# schChaves.net
KiCad netlist of a schematic drawn in Altium Designer
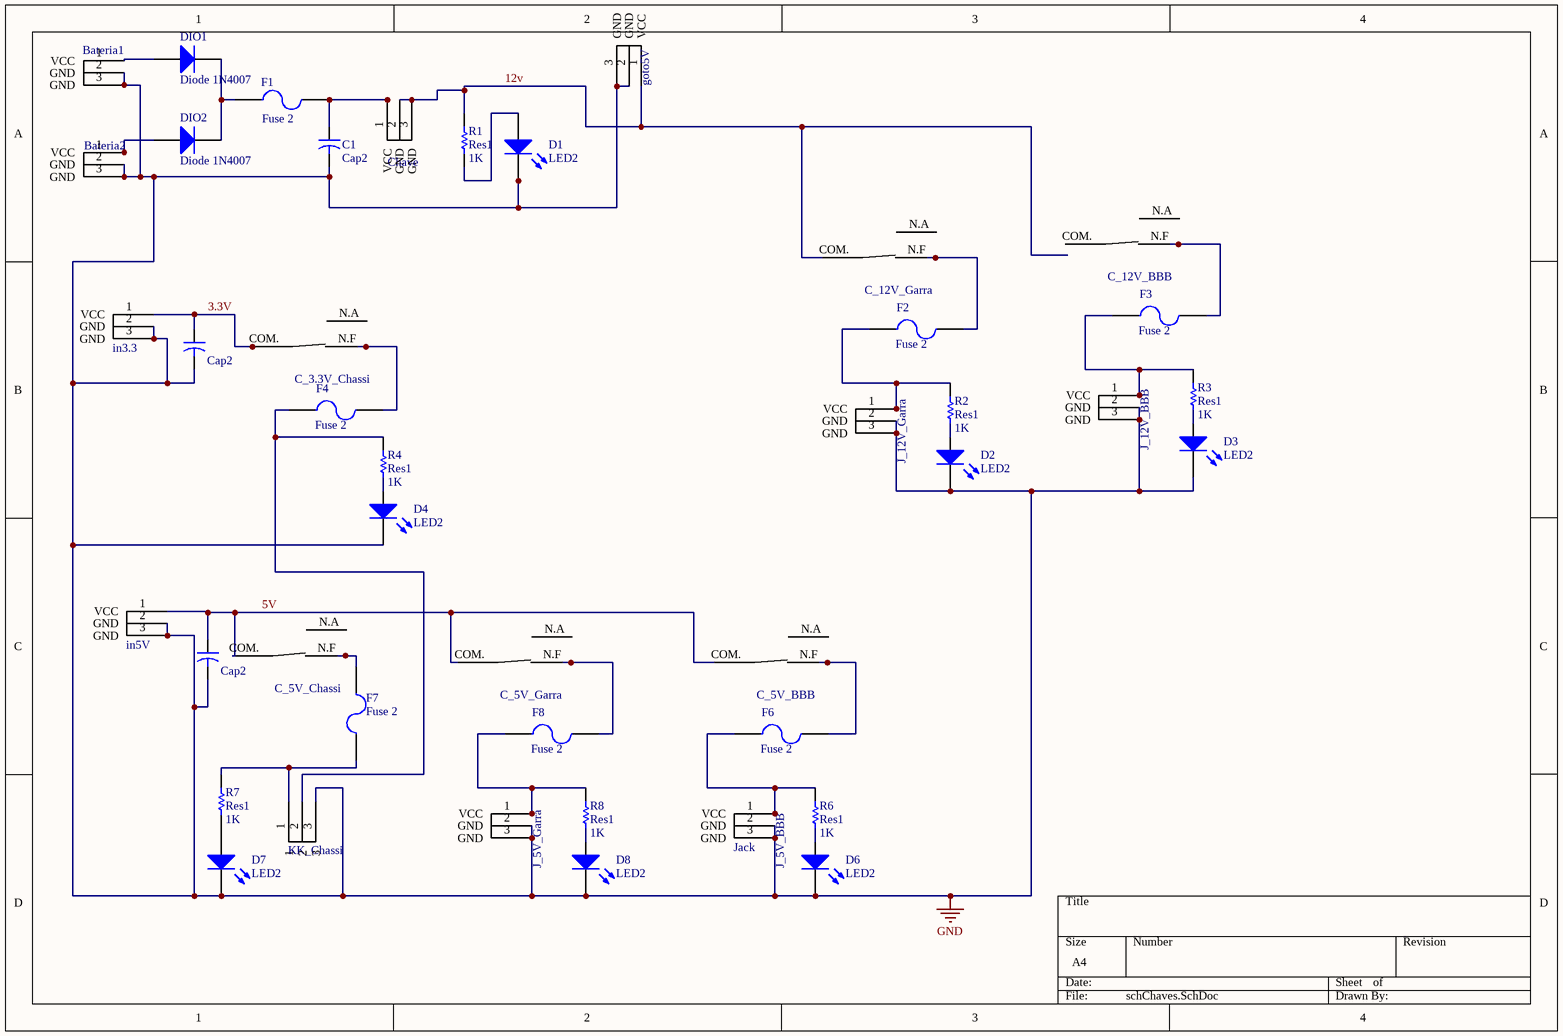
[diagram p0: schChaves.SchDoc]

(export (version "E")
  (design (tool "Eeschema 10.0.6"))
  (components
    (comp (ref "Bateria1")
      (value "Jack")
      (footprint "JACK J4")
      (libsource (lib "Componentes_Open") (part "Jack"))
    )
    (comp (ref "Bateria2")
      (value "Jack")
      (footprint "JACK J4")
      (libsource (lib "Componentes_Open") (part "Jack"))
    )
    (comp (ref "C1")
      (value "Cap2")
      (footprint "RAD-0.2")
      (description "Capacitor")
      (fields (field (name "PUBLISHER") "Altium Limited"))
      (libsource (lib "Miscellaneous Devices") (part "Cap2"))
    )
    (comp (ref "C3")
      (value "Cap2")
      (footprint "RAD-0.2")
      (description "Capacitor")
      (fields (field (name "PUBLISHER") "Altium Limited"))
      (libsource (lib "Miscellaneous Devices") (part "Cap2"))
    )
    (comp (ref "C5")
      (value "Cap2")
      (footprint "RAD-0.2")
      (description "Capacitor")
      (fields (field (name "PUBLISHER") "Altium Limited"))
      (libsource (lib "Miscellaneous Devices") (part "Cap2"))
    )
    (comp (ref "Chave")
      (value "Jack")
      (footprint "JACK J4")
      (libsource (lib "Componentes_Open") (part "Jack"))
    )
    (comp (ref "C_3.3V_Chassi")
      (value "Chave")
      (footprint "Chave")
      (libsource (lib "Componentes_Open") (part "Chave"))
    )
    (comp (ref "C_5V_BBB")
      (value "Chave")
      (footprint "Chave")
      (libsource (lib "Componentes_Open") (part "Chave"))
    )
    (comp (ref "C_5V_Chassi")
      (value "Chave")
      (footprint "Chave")
      (libsource (lib "Componentes_Open") (part "Chave"))
    )
    (comp (ref "C_5V_Garra")
      (value "Chave")
      (footprint "Chave")
      (libsource (lib "Componentes_Open") (part "Chave"))
    )
    (comp (ref "C_12V_BBB")
      (value "Chave")
      (footprint "Chave")
      (libsource (lib "Componentes_Open") (part "Chave"))
    )
    (comp (ref "C_12V_Garra")
      (value "Chave")
      (footprint "Chave")
      (libsource (lib "Componentes_Open") (part "Chave"))
    )
    (comp (ref "D1")
      (value "LED2")
      (footprint "3.2X1.6X1.1")
      (description "Typical RED, GREEN, YELLOW, AMBER GaAs LED")
      (fields (field (name "PUBLISHER") "Altium Limited"))
      (libsource (lib "Miscellaneous Devices") (part "LED2"))
    )
    (comp (ref "D2")
      (value "LED2")
      (footprint "3.2X1.6X1.1")
      (description "Typical RED, GREEN, YELLOW, AMBER GaAs LED")
      (fields (field (name "PUBLISHER") "Altium Limited"))
      (libsource (lib "Miscellaneous Devices") (part "LED2"))
    )
    (comp (ref "D3")
      (value "LED2")
      (footprint "3.2X1.6X1.1")
      (description "Typical RED, GREEN, YELLOW, AMBER GaAs LED")
      (fields (field (name "PUBLISHER") "Altium Limited"))
      (libsource (lib "Miscellaneous Devices") (part "LED2"))
    )
    (comp (ref "D4")
      (value "LED2")
      (footprint "3.2X1.6X1.1")
      (description "Typical RED, GREEN, YELLOW, AMBER GaAs LED")
      (fields (field (name "PUBLISHER") "Altium Limited"))
      (libsource (lib "Miscellaneous Devices") (part "LED2"))
    )
    (comp (ref "D6")
      (value "LED2")
      (footprint "3.2X1.6X1.1")
      (description "Typical RED, GREEN, YELLOW, AMBER GaAs LED")
      (fields (field (name "PUBLISHER") "Altium Limited"))
      (libsource (lib "Miscellaneous Devices") (part "LED2"))
    )
    (comp (ref "D7")
      (value "LED2")
      (footprint "3.2X1.6X1.1")
      (description "Typical RED, GREEN, YELLOW, AMBER GaAs LED")
      (fields (field (name "PUBLISHER") "Altium Limited"))
      (libsource (lib "Miscellaneous Devices") (part "LED2"))
    )
    (comp (ref "D8")
      (value "LED2")
      (footprint "3.2X1.6X1.1")
      (description "Typical RED, GREEN, YELLOW, AMBER GaAs LED")
      (fields (field (name "PUBLISHER") "Altium Limited"))
      (libsource (lib "Miscellaneous Devices") (part "LED2"))
    )
    (comp (ref "DIO1")
      (value "Diode 1N4007")
      (footprint "DO-41")
      (description "1 Amp General Purpose Rectifier")
      (fields (field (name "PUBLISHER") "Altium Limited"))
      (libsource (lib "Miscellaneous Devices") (part "Diode 1N4007"))
    )
    (comp (ref "DIO2")
      (value "Diode 1N4007")
      (footprint "DO-41")
      (description "1 Amp General Purpose Rectifier")
      (fields (field (name "PUBLISHER") "Altium Limited"))
      (libsource (lib "Miscellaneous Devices") (part "Diode 1N4007"))
    )
    (comp (ref "F1")
      (value "Fuse 2")
      (footprint "Fusivel")
      (description "Fuse")
      (fields (field (name "PUBLISHER") "Altium Limited"))
      (libsource (lib "Miscellaneous Devices") (part "Fuse 2"))
    )
    (comp (ref "F2")
      (value "Fuse 2")
      (footprint "Fusivel")
      (description "Fuse")
      (fields (field (name "PUBLISHER") "Altium Limited"))
      (libsource (lib "Miscellaneous Devices") (part "Fuse 2"))
    )
    (comp (ref "F3")
      (value "Fuse 2")
      (footprint "Fusivel")
      (description "Fuse")
      (fields (field (name "PUBLISHER") "Altium Limited"))
      (libsource (lib "Miscellaneous Devices") (part "Fuse 2"))
    )
    (comp (ref "F4")
      (value "Fuse 2")
      (footprint "Fusivel")
      (description "Fuse")
      (fields (field (name "PUBLISHER") "Altium Limited"))
      (libsource (lib "Miscellaneous Devices") (part "Fuse 2"))
    )
    (comp (ref "F6")
      (value "Fuse 2")
      (footprint "Fusivel")
      (description "Fuse")
      (fields (field (name "PUBLISHER") "Altium Limited"))
      (libsource (lib "Miscellaneous Devices") (part "Fuse 2"))
    )
    (comp (ref "F7")
      (value "Fuse 2")
      (footprint "Fusivel")
      (description "Fuse")
      (fields (field (name "PUBLISHER") "Altium Limited"))
      (libsource (lib "Miscellaneous Devices") (part "Fuse 2"))
    )
    (comp (ref "F8")
      (value "Fuse 2")
      (footprint "Fusivel")
      (description "Fuse")
      (fields (field (name "PUBLISHER") "Altium Limited"))
      (libsource (lib "Miscellaneous Devices") (part "Fuse 2"))
    )
    (comp (ref "goto5V")
      (value "Jack")
      (footprint "JACK J4")
      (libsource (lib "Componentes_Open") (part "Jack"))
    )
    (comp (ref "in3.3")
      (value "Jack")
      (footprint "JACK J4")
      (libsource (lib "Componentes_Open") (part "Jack"))
    )
    (comp (ref "in5V")
      (value "Jack")
      (footprint "JACK J4")
      (libsource (lib "Componentes_Open") (part "Jack"))
    )
    (comp (ref "J_5V_BBB")
      (value "Jack")
      (footprint "JACK J4")
      (libsource (lib "Componentes_Open") (part "Jack"))
    )
    (comp (ref "J_5V_Garra")
      (value "Jack")
      (footprint "JACK J4")
      (libsource (lib "Componentes_Open") (part "Jack"))
    )
    (comp (ref "J_12V_BBB")
      (value "Jack")
      (footprint "JACK J4")
      (libsource (lib "Componentes_Open") (part "Jack"))
    )
    (comp (ref "J_12V_Garra")
      (value "Jack")
      (footprint "JACK J4")
      (libsource (lib "Componentes_Open") (part "Jack"))
    )
    (comp (ref "KK_Chassi")
      (value "KK3")
      (footprint "3-vias")
      (libsource (lib "Componentes_Open") (part "KK3Vias"))
    )
    (comp (ref "R1")
      (value "Res1")
      (footprint "AXIAL-0.3")
      (description "Resistor")
      (fields (field (name "ALTIUM_VALUE") "1K") (field (name "PUBLISHER") "Altium Limited"))
      (libsource (lib "Miscellaneous Devices") (part "Res1"))
    )
    (comp (ref "R2")
      (value "Res1")
      (footprint "AXIAL-0.3")
      (description "Resistor")
      (fields (field (name "ALTIUM_VALUE") "1K") (field (name "PUBLISHER") "Altium Limited"))
      (libsource (lib "Miscellaneous Devices") (part "Res1"))
    )
    (comp (ref "R3")
      (value "Res1")
      (footprint "AXIAL-0.3")
      (description "Resistor")
      (fields (field (name "ALTIUM_VALUE") "1K") (field (name "PUBLISHER") "Altium Limited"))
      (libsource (lib "Miscellaneous Devices") (part "Res1"))
    )
    (comp (ref "R4")
      (value "Res1")
      (footprint "AXIAL-0.3")
      (description "Resistor")
      (fields (field (name "ALTIUM_VALUE") "1K") (field (name "PUBLISHER") "Altium Limited"))
      (libsource (lib "Miscellaneous Devices") (part "Res1"))
    )
    (comp (ref "R6")
      (value "Res1")
      (footprint "AXIAL-0.3")
      (description "Resistor")
      (fields (field (name "ALTIUM_VALUE") "1K") (field (name "PUBLISHER") "Altium Limited"))
      (libsource (lib "Miscellaneous Devices") (part "Res1"))
    )
    (comp (ref "R7")
      (value "Res1")
      (footprint "AXIAL-0.3")
      (description "Resistor")
      (fields (field (name "ALTIUM_VALUE") "1K") (field (name "PUBLISHER") "Altium Limited"))
      (libsource (lib "Miscellaneous Devices") (part "Res1"))
    )
    (comp (ref "R8")
      (value "Res1")
      (footprint "AXIAL-0.3")
      (description "Resistor")
      (fields (field (name "ALTIUM_VALUE") "1K") (field (name "PUBLISHER") "Altium Limited"))
      (libsource (lib "Miscellaneous Devices") (part "Res1"))
    )
  )
  (nets
    (net (code "1") (name "/3.3V") (class "Default")
      (node (ref "C3") (pin "1") (pinfunction "1_1") (pintype "passive"))
      (node (ref "C_3.3V_Chassi") (pin "COM.") (pinfunction "COM_COM.") (pintype "passive"))
      (node (ref "in3.3") (pin "1") (pinfunction "VCC_1") (pintype "passive"))
    )
    (net (code "2") (name "/5V") (class "Default")
      (node (ref "C5") (pin "1") (pinfunction "1_1") (pintype "passive"))
      (node (ref "C_5V_BBB") (pin "COM.") (pinfunction "COM_COM.") (pintype "passive"))
      (node (ref "C_5V_Chassi") (pin "COM.") (pinfunction "COM_COM.") (pintype "passive"))
      (node (ref "C_5V_Garra") (pin "COM.") (pinfunction "COM_COM.") (pintype "passive"))
      (node (ref "in5V") (pin "1") (pinfunction "VCC_1") (pintype "passive"))
    )
    (net (code "3") (name "/12v") (class "Default")
      (node (ref "C_12V_Garra") (pin "COM.") (pinfunction "COM_COM.") (pintype "passive"))
      (node (ref "Chave") (pin "2") (pinfunction "GND_2") (pintype "passive"))
      (node (ref "Chave") (pin "3") (pinfunction "GND_3") (pintype "passive"))
      (node (ref "R1") (pin "2") (pinfunction "2_2") (pintype "passive"))
      (node (ref "goto5V") (pin "1") (pinfunction "VCC_1") (pintype "passive"))
    )
    (net (code "4") (name "GND") (class "Default")
      (node (ref "Bateria1") (pin "2") (pinfunction "GND_2") (pintype "passive"))
      (node (ref "Bateria1") (pin "3") (pinfunction "GND_3") (pintype "passive"))
      (node (ref "Bateria2") (pin "2") (pinfunction "GND_2") (pintype "passive"))
      (node (ref "Bateria2") (pin "3") (pinfunction "GND_3") (pintype "passive"))
      (node (ref "C1") (pin "2") (pinfunction "2_2") (pintype "passive"))
      (node (ref "C3") (pin "2") (pinfunction "2_2") (pintype "passive"))
      (node (ref "C5") (pin "2") (pinfunction "2_2") (pintype "passive"))
      (node (ref "D1") (pin "2") (pinfunction "K_2") (pintype "passive"))
      (node (ref "D2") (pin "2") (pinfunction "K_2") (pintype "passive"))
      (node (ref "D3") (pin "2") (pinfunction "K_2") (pintype "passive"))
      (node (ref "D4") (pin "2") (pinfunction "K_2") (pintype "passive"))
      (node (ref "D6") (pin "2") (pinfunction "K_2") (pintype "passive"))
      (node (ref "D7") (pin "2") (pinfunction "K_2") (pintype "passive"))
      (node (ref "D8") (pin "2") (pinfunction "K_2") (pintype "passive"))
      (node (ref "J_12V_BBB") (pin "2") (pinfunction "GND_2") (pintype "passive"))
      (node (ref "J_12V_BBB") (pin "3") (pinfunction "GND_3") (pintype "passive"))
      (node (ref "J_12V_Garra") (pin "2") (pinfunction "GND_2") (pintype "passive"))
      (node (ref "J_12V_Garra") (pin "3") (pinfunction "GND_3") (pintype "passive"))
      (node (ref "J_5V_BBB") (pin "2") (pinfunction "GND_2") (pintype "passive"))
      (node (ref "J_5V_BBB") (pin "3") (pinfunction "GND_3") (pintype "passive"))
      (node (ref "J_5V_Garra") (pin "2") (pinfunction "GND_2") (pintype "passive"))
      (node (ref "J_5V_Garra") (pin "3") (pinfunction "GND_3") (pintype "passive"))
      (node (ref "KK_Chassi") (pin "3") (pinfunction "3_3") (pintype "passive"))
      (node (ref "goto5V") (pin "2") (pinfunction "GND_2") (pintype "passive"))
      (node (ref "goto5V") (pin "3") (pinfunction "GND_3") (pintype "passive"))
      (node (ref "in3.3") (pin "2") (pinfunction "GND_2") (pintype "passive"))
      (node (ref "in3.3") (pin "3") (pinfunction "GND_3") (pintype "passive"))
      (node (ref "in5V") (pin "2") (pinfunction "GND_2") (pintype "passive"))
      (node (ref "in5V") (pin "3") (pinfunction "GND_3") (pintype "passive"))
    )
    (net (code "5") (name "Net-(Bateria1-VCC)") (class "Default")
      (node (ref "Bateria1") (pin "1") (pinfunction "VCC_1") (pintype "passive"))
      (node (ref "DIO1") (pin "1") (pinfunction "A_1") (pintype "passive"))
    )
    (net (code "6") (name "Net-(Bateria2-VCC)") (class "Default")
      (node (ref "Bateria2") (pin "1") (pinfunction "VCC_1") (pintype "passive"))
      (node (ref "DIO2") (pin "1") (pinfunction "A_1") (pintype "passive"))
    )
    (net (code "7") (name "Net-(C_3.3V_Chassi-PadN.F)") (class "Default")
      (node (ref "C_3.3V_Chassi") (pin "N.F") (pinfunction "N.F_N.F") (pintype "passive"))
      (node (ref "F4") (pin "2") (pinfunction "2_2") (pintype "passive"))
    )
    (net (code "8") (name "Net-(C_5V_BBB-PadN.F)") (class "Default")
      (node (ref "C_5V_BBB") (pin "N.F") (pinfunction "N.F_N.F") (pintype "passive"))
      (node (ref "F6") (pin "2") (pinfunction "2_2") (pintype "passive"))
    )
    (net (code "9") (name "Net-(C_5V_Chassi-PadN.F)") (class "Default")
      (node (ref "C_5V_Chassi") (pin "N.F") (pinfunction "N.F_N.F") (pintype "passive"))
      (node (ref "F7") (pin "1") (pinfunction "1_1") (pintype "passive"))
    )
    (net (code "10") (name "Net-(C_5V_Garra-PadN.F)") (class "Default")
      (node (ref "C_5V_Garra") (pin "N.F") (pinfunction "N.F_N.F") (pintype "passive"))
      (node (ref "F8") (pin "2") (pinfunction "2_2") (pintype "passive"))
    )
    (net (code "11") (name "Net-(C_12V_BBB-PadN.F)") (class "Default")
      (node (ref "C_12V_BBB") (pin "N.F") (pinfunction "N.F_N.F") (pintype "passive"))
      (node (ref "F3") (pin "2") (pinfunction "2_2") (pintype "passive"))
    )
    (net (code "12") (name "Net-(C_12V_Garra-PadN.F)") (class "Default")
      (node (ref "C_12V_Garra") (pin "N.F") (pinfunction "N.F_N.F") (pintype "passive"))
      (node (ref "F2") (pin "2") (pinfunction "2_2") (pintype "passive"))
    )
    (net (code "13") (name "Net-(Chave-VCC)") (class "Default")
      (node (ref "C1") (pin "1") (pinfunction "1_1") (pintype "passive"))
      (node (ref "Chave") (pin "1") (pinfunction "VCC_1") (pintype "passive"))
      (node (ref "F1") (pin "2") (pinfunction "2_2") (pintype "passive"))
    )
    (net (code "14") (name "Net-(D1-A)") (class "Default")
      (node (ref "D1") (pin "1") (pinfunction "A_1") (pintype "passive"))
      (node (ref "R1") (pin "1") (pinfunction "1_1") (pintype "passive"))
    )
    (net (code "15") (name "Net-(D2-A)") (class "Default")
      (node (ref "D2") (pin "1") (pinfunction "A_1") (pintype "passive"))
      (node (ref "R2") (pin "1") (pinfunction "1_1") (pintype "passive"))
    )
    (net (code "16") (name "Net-(D3-A)") (class "Default")
      (node (ref "D3") (pin "1") (pinfunction "A_1") (pintype "passive"))
      (node (ref "R3") (pin "1") (pinfunction "1_1") (pintype "passive"))
    )
    (net (code "17") (name "Net-(D4-A)") (class "Default")
      (node (ref "D4") (pin "1") (pinfunction "A_1") (pintype "passive"))
      (node (ref "R4") (pin "1") (pinfunction "1_1") (pintype "passive"))
    )
    (net (code "18") (name "Net-(D6-A)") (class "Default")
      (node (ref "D6") (pin "1") (pinfunction "A_1") (pintype "passive"))
      (node (ref "R6") (pin "1") (pinfunction "1_1") (pintype "passive"))
    )
    (net (code "19") (name "Net-(D7-A)") (class "Default")
      (node (ref "D7") (pin "1") (pinfunction "A_1") (pintype "passive"))
      (node (ref "R7") (pin "1") (pinfunction "1_1") (pintype "passive"))
    )
    (net (code "20") (name "Net-(D8-A)") (class "Default")
      (node (ref "D8") (pin "1") (pinfunction "A_1") (pintype "passive"))
      (node (ref "R8") (pin "1") (pinfunction "1_1") (pintype "passive"))
    )
    (net (code "21") (name "Net-(DIO1-K)") (class "Default")
      (node (ref "DIO1") (pin "2") (pinfunction "K_2") (pintype "passive"))
      (node (ref "DIO2") (pin "2") (pinfunction "K_2") (pintype "passive"))
      (node (ref "F1") (pin "1") (pinfunction "1_1") (pintype "passive"))
    )
    (net (code "22") (name "Net-(F4-Pad1)") (class "Default")
      (node (ref "F4") (pin "1") (pinfunction "1_1") (pintype "passive"))
      (node (ref "KK_Chassi") (pin "2") (pinfunction "2_2") (pintype "passive"))
      (node (ref "R4") (pin "2") (pinfunction "2_2") (pintype "passive"))
    )
    (net (code "23") (name "Net-(F7-Pad2)") (class "Default")
      (node (ref "F7") (pin "2") (pinfunction "2_2") (pintype "passive"))
      (node (ref "KK_Chassi") (pin "1") (pinfunction "1_1") (pintype "passive"))
      (node (ref "R7") (pin "2") (pinfunction "2_2") (pintype "passive"))
    )
    (net (code "24") (name "Net-(J_5V_BBB-VCC)") (class "Default")
      (node (ref "F6") (pin "1") (pinfunction "1_1") (pintype "passive"))
      (node (ref "J_5V_BBB") (pin "1") (pinfunction "VCC_1") (pintype "passive"))
      (node (ref "R6") (pin "2") (pinfunction "2_2") (pintype "passive"))
    )
    (net (code "25") (name "Net-(J_5V_Garra-VCC)") (class "Default")
      (node (ref "F8") (pin "1") (pinfunction "1_1") (pintype "passive"))
      (node (ref "J_5V_Garra") (pin "1") (pinfunction "VCC_1") (pintype "passive"))
      (node (ref "R8") (pin "2") (pinfunction "2_2") (pintype "passive"))
    )
    (net (code "26") (name "Net-(J_12V_BBB-VCC)") (class "Default")
      (node (ref "F3") (pin "1") (pinfunction "1_1") (pintype "passive"))
      (node (ref "J_12V_BBB") (pin "1") (pinfunction "VCC_1") (pintype "passive"))
      (node (ref "R3") (pin "2") (pinfunction "2_2") (pintype "passive"))
    )
    (net (code "27") (name "Net-(J_12V_Garra-VCC)") (class "Default")
      (node (ref "F2") (pin "1") (pinfunction "1_1") (pintype "passive"))
      (node (ref "J_12V_Garra") (pin "1") (pinfunction "VCC_1") (pintype "passive"))
      (node (ref "R2") (pin "2") (pinfunction "2_2") (pintype "passive"))
    )
    (net (code "28") (name "unconnected-(C_3.3V_Chassi-PadN.A)") (class "Default")
      (node (ref "C_3.3V_Chassi") (pin "N.A") (pinfunction "N.A_N.A") (pintype "passive"))
    )
    (net (code "29") (name "unconnected-(C_5V_BBB-PadN.A)") (class "Default")
      (node (ref "C_5V_BBB") (pin "N.A") (pinfunction "N.A_N.A") (pintype "passive"))
    )
    (net (code "30") (name "unconnected-(C_5V_Chassi-PadN.A)") (class "Default")
      (node (ref "C_5V_Chassi") (pin "N.A") (pinfunction "N.A_N.A") (pintype "passive"))
    )
    (net (code "31") (name "unconnected-(C_5V_Garra-PadN.A)") (class "Default")
      (node (ref "C_5V_Garra") (pin "N.A") (pinfunction "N.A_N.A") (pintype "passive"))
    )
    (net (code "32") (name "unconnected-(C_12V_BBB-COM-PadCOM.)") (class "Default")
      (node (ref "C_12V_BBB") (pin "COM.") (pinfunction "COM_COM.") (pintype "passive"))
    )
    (net (code "33") (name "unconnected-(C_12V_BBB-PadN.A)") (class "Default")
      (node (ref "C_12V_BBB") (pin "N.A") (pinfunction "N.A_N.A") (pintype "passive"))
    )
    (net (code "34") (name "unconnected-(C_12V_Garra-PadN.A)") (class "Default")
      (node (ref "C_12V_Garra") (pin "N.A") (pinfunction "N.A_N.A") (pintype "passive"))
    )
  )
)
